# Audio_Codecs_v1.net
KiCad netlist of a schematic drawn in Altium Designer
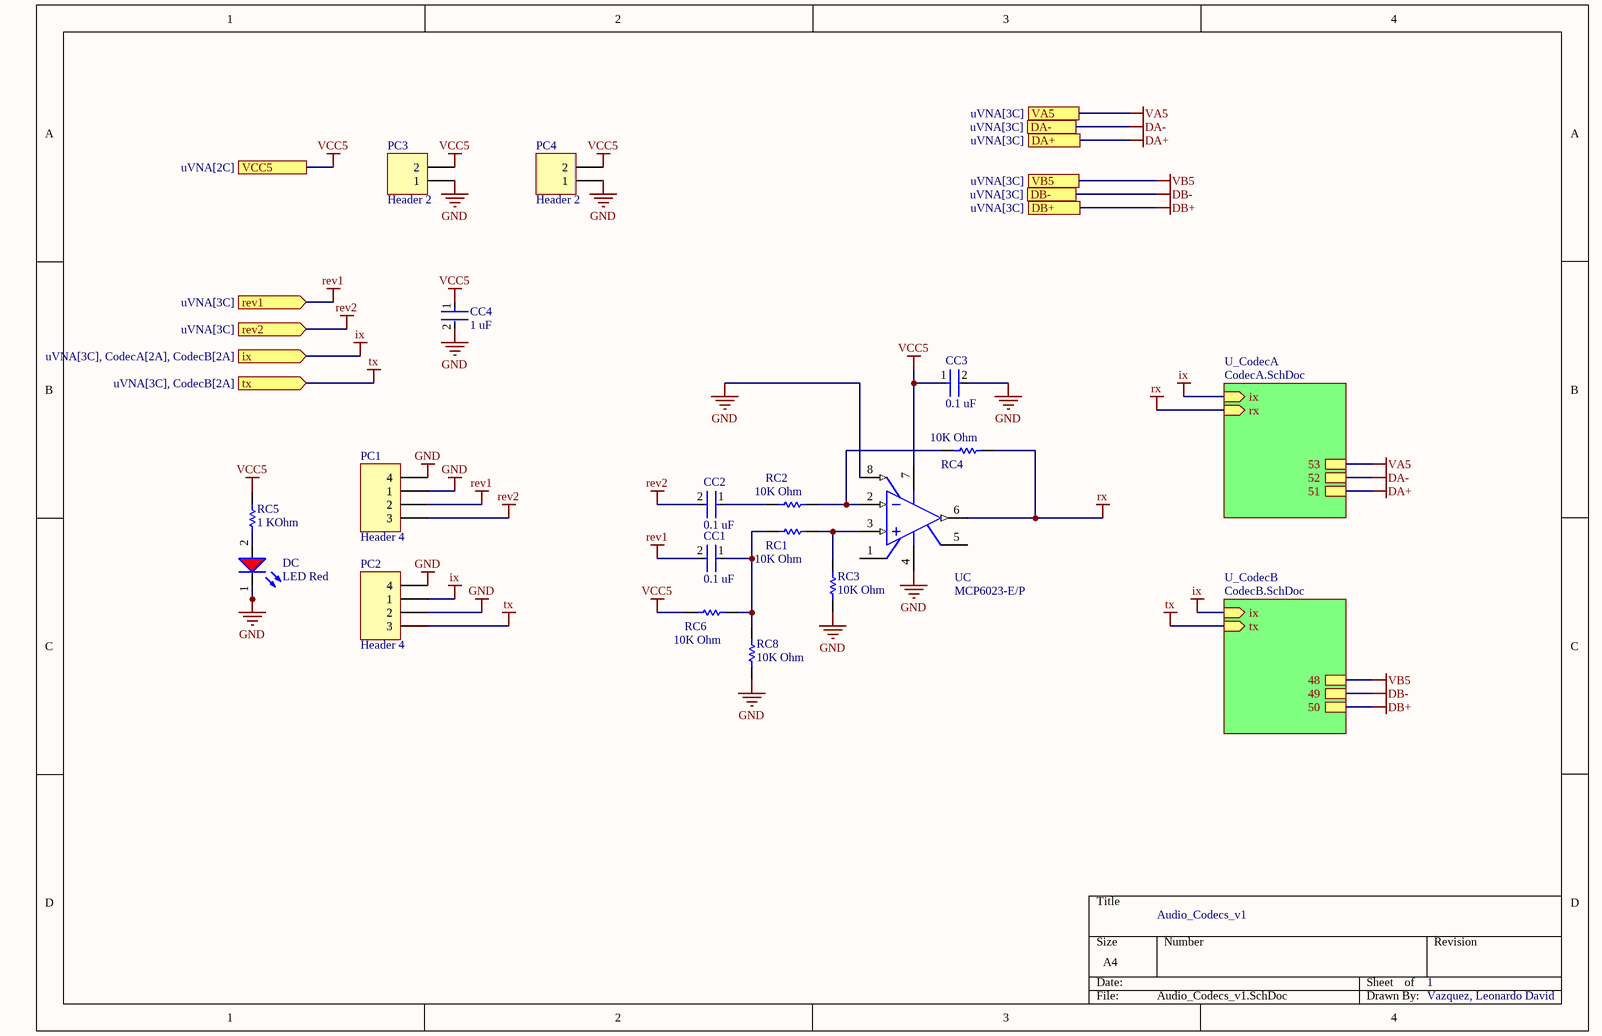
[diagram p0: Audio_Codecs_v1.SchDoc]

(export (version "E")
  (design (tool "Eeschema 10.0.6"))
  (components
    (comp (ref "CC1")
      (value "0.1 uF")
      (footprint "FP-CC0805-0_85-MFG")
      (description "CAP CER 0.1UF 50V X7R 0805")
      (fields (field (name "TOLERANCE") "0.1") (field (name "MANUFACTURER PART NUMBER") "CC0805KRX7R9BB104"))
      (libsource (lib "Altium Content Vault") (part "11868f565c42a9108669ba33697ecf6"))
    )
    (comp (ref "CC2")
      (value "0.1 uF")
      (footprint "FP-CC0805-0_85-MFG")
      (description "CAP CER 0.1UF 50V X7R 0805")
      (fields (field (name "TOLERANCE") "0.1") (field (name "MANUFACTURER PART NUMBER") "CC0805KRX7R9BB104"))
      (libsource (lib "Altium Content Vault") (part "11868f565c42a9108669ba33697ecf6"))
    )
    (comp (ref "CC3")
      (value "0.1 uF")
      (footprint "FP-CC0805-0_85-MFG")
      (description "CAP CER 0.1UF 50V X7R 0805")
      (fields (field (name "TOLERANCE") "0.1") (field (name "MANUFACTURER PART NUMBER") "CC0805KRX7R9BB104"))
      (libsource (lib "Altium Content Vault") (part "11868f565c42a9108669ba33697ecf6"))
    )
    (comp (ref "CC4")
      (value "1 uF")
      (footprint "FP-CC0805-0_85-MFG")
      (description "CAP CER 0.1UF 50V X7R 0805")
      (fields (field (name "TOLERANCE") "0.1") (field (name "MANUFACTURER PART NUMBER") "CC0805KRX7R9BB104"))
      (libsource (lib "Altium Content Vault") (part "11868f565c42a9108669ba33697ecf6"))
    )
    (comp (ref "DC")
      (value "LED Red")
      (footprint "WL-SMCW_0805_150080xx75000")
      (libsource (lib "Altium Content Vault") (part "LED_Red_2A-1K"))
    )
    (comp (ref "PC1")
      (value "Header 4")
      (footprint "HDR1X4")
      (description "Header, 4-Pin")
      (fields (field (name "PUBLISHER") "Altium Limited"))
      (libsource (lib "Miscellaneous Connectors") (part "Header 4"))
    )
    (comp (ref "PC2")
      (value "Header 4")
      (footprint "HDR1X4")
      (description "Header, 4-Pin")
      (fields (field (name "PUBLISHER") "Altium Limited"))
      (libsource (lib "Miscellaneous Connectors") (part "Header 4"))
    )
    (comp (ref "PC3")
      (value "Header 2")
      (footprint "HDR1X2")
      (description "Header, 2-Pin")
      (fields (field (name "PUBLISHER") "Altium Limited"))
      (libsource (lib "Miscellaneous Connectors") (part "Header 2"))
    )
    (comp (ref "PC4")
      (value "Header 2")
      (footprint "HDR1X2")
      (description "Header, 2-Pin")
      (fields (field (name "PUBLISHER") "Altium Limited"))
      (libsource (lib "Miscellaneous Connectors") (part "Header 2"))
    )
    (comp (ref "RC1")
      (value "10K Ohm")
      (footprint "RESC2013X60X40ML20T25")
      (fields (field (name "MANUFACTURER") "Panasonic") (field (name "PART NUMBER") "ERA6AEB101V"))
      (libsource (lib "Altium Content Vault") (part "RES"))
    )
    (comp (ref "RC2")
      (value "10K Ohm")
      (footprint "RESC2013X60X40ML20T25")
      (fields (field (name "MANUFACTURER") "Panasonic") (field (name "PART NUMBER") "ERA6AEB101V"))
      (libsource (lib "Altium Content Vault") (part "RES"))
    )
    (comp (ref "RC3")
      (value "10K Ohm")
      (footprint "RESC2013X60X40ML20T25")
      (fields (field (name "MANUFACTURER") "Panasonic") (field (name "PART NUMBER") "ERA6AEB101V"))
      (libsource (lib "Altium Content Vault") (part "RES"))
    )
    (comp (ref "RC4")
      (value "10K Ohm")
      (footprint "RESC2013X60X40ML20T25")
      (fields (field (name "MANUFACTURER") "Panasonic") (field (name "PART NUMBER") "ERA6AEB101V"))
      (libsource (lib "Altium Content Vault") (part "RES"))
    )
    (comp (ref "RC5")
      (value "1 KOhm")
      (footprint "RESC2013X60X40ML20T25")
      (fields (field (name "MANUFACTURER") "Panasonic") (field (name "PART NUMBER") "ERA6AEB101V"))
      (libsource (lib "Altium Content Vault") (part "RES"))
    )
    (comp (ref "RC6")
      (value "10K Ohm")
      (footprint "RESC2013X60X40ML20T25")
      (fields (field (name "MANUFACTURER") "Panasonic") (field (name "PART NUMBER") "ERA6AEB101V"))
      (libsource (lib "Altium Content Vault") (part "RES"))
    )
    (comp (ref "RC8")
      (value "10K Ohm")
      (footprint "RESC2013X60X40ML20T25")
      (fields (field (name "MANUFACTURER") "Panasonic") (field (name "PART NUMBER") "ERA6AEB101V"))
      (libsource (lib "Altium Content Vault") (part "RES"))
    )
    (comp (ref "UC")
      (value "MCP6023-E/P")
      (footprint "PDIP300-P8")
      (description "None")
      (libsource (lib "Altium Content Vault") (part "AMP-OPA-MCP6023-IL8"))
    )
  )
  (nets
    (net (code "5") (name "GND") (class "Default")
      (node (ref "CC3") (pin "2") (pinfunction "2_2") (pintype "passive"))
      (node (ref "CC4") (pin "2") (pinfunction "2_2") (pintype "passive"))
      (node (ref "DC") (pin "1") (pinfunction "K_1") (pintype "passive"))
      (node (ref "PC1") (pin "1") (pinfunction "1_1") (pintype "passive"))
      (node (ref "PC1") (pin "4") (pinfunction "4_4") (pintype "passive"))
      (node (ref "PC2") (pin "2") (pinfunction "2_2") (pintype "passive"))
      (node (ref "PC2") (pin "4") (pinfunction "4_4") (pintype "passive"))
      (node (ref "PC3") (pin "1") (pinfunction "1_1") (pintype "passive"))
      (node (ref "PC4") (pin "1") (pinfunction "1_1") (pintype "passive"))
      (node (ref "RC3") (pin "2") (pinfunction "2_2") (pintype "passive"))
      (node (ref "RC8") (pin "2") (pinfunction "2_2") (pintype "passive"))
      (node (ref "UC") (pin "4") (pinfunction "VSS_4") (pintype "power_in"))
      (node (ref "UC") (pin "8") (pinfunction "~{CS}_8") (pintype "input"))
    )
    (net (code "6") (name "Net-(CC1-Pad1)") (class "Default")
      (node (ref "CC1") (pin "1") (pinfunction "1_1") (pintype "passive"))
      (node (ref "RC1") (pin "2") (pinfunction "2_2") (pintype "passive"))
      (node (ref "RC6") (pin "1") (pinfunction "1_1") (pintype "passive"))
      (node (ref "RC8") (pin "1") (pinfunction "1_1") (pintype "passive"))
    )
    (net (code "7") (name "Net-(CC2-Pad1)") (class "Default")
      (node (ref "CC2") (pin "1") (pinfunction "1_1") (pintype "passive"))
      (node (ref "RC2") (pin "2") (pinfunction "2_2") (pintype "passive"))
    )
    (net (code "8") (name "Net-(DC-A)") (class "Default")
      (node (ref "DC") (pin "2") (pinfunction "A_2") (pintype "passive"))
      (node (ref "RC5") (pin "1") (pinfunction "1_1") (pintype "passive"))
    )
    (net (code "9") (name "Net-(UC-VIN+)") (class "Default")
      (node (ref "RC1") (pin "1") (pinfunction "1_1") (pintype "passive"))
      (node (ref "RC3") (pin "1") (pinfunction "1_1") (pintype "passive"))
      (node (ref "UC") (pin "3") (pinfunction "VIN+_3") (pintype "input"))
    )
    (net (code "10") (name "Net-(UC-VIN-)") (class "Default")
      (node (ref "RC2") (pin "1") (pinfunction "1_1") (pintype "passive"))
      (node (ref "RC4") (pin "2") (pinfunction "2_2") (pintype "passive"))
      (node (ref "UC") (pin "2") (pinfunction "VIN-_2") (pintype "input"))
    )
    (net (code "13") (name "VCC5") (class "Default")
      (node (ref "CC3") (pin "1") (pinfunction "1_1") (pintype "passive"))
      (node (ref "CC4") (pin "1") (pinfunction "1_1") (pintype "passive"))
      (node (ref "PC3") (pin "2") (pinfunction "2_2") (pintype "passive"))
      (node (ref "PC4") (pin "2") (pinfunction "2_2") (pintype "passive"))
      (node (ref "RC5") (pin "2") (pinfunction "2_2") (pintype "passive"))
      (node (ref "RC6") (pin "2") (pinfunction "2_2") (pintype "passive"))
      (node (ref "UC") (pin "7") (pinfunction "VDD_7") (pintype "power_in"))
    )
    (net (code "14") (name "ix") (class "Default")
      (node (ref "PC2") (pin "1") (pinfunction "1_1") (pintype "passive"))
    )
    (net (code "15") (name "rev1") (class "Default")
      (node (ref "CC1") (pin "2") (pinfunction "2_2") (pintype "passive"))
      (node (ref "PC1") (pin "2") (pinfunction "2_2") (pintype "passive"))
    )
    (net (code "16") (name "rev2") (class "Default")
      (node (ref "CC2") (pin "2") (pinfunction "2_2") (pintype "passive"))
      (node (ref "PC1") (pin "3") (pinfunction "3_3") (pintype "passive"))
    )
    (net (code "17") (name "rx") (class "Default")
      (node (ref "RC4") (pin "1") (pinfunction "1_1") (pintype "passive"))
      (node (ref "UC") (pin "6") (pinfunction "VOUT_6") (pintype "output"))
    )
    (net (code "18") (name "tx") (class "Default")
      (node (ref "PC2") (pin "3") (pinfunction "3_3") (pintype "passive"))
    )
    (net (code "19") (name "unconnected-(UC-NC-Pad1)") (class "Default")
      (node (ref "UC") (pin "1") (pinfunction "NC_1") (pintype "passive"))
    )
    (net (code "20") (name "unconnected-(UC-VREF-Pad5)") (class "Default")
      (node (ref "UC") (pin "5") (pinfunction "VREF_5") (pintype "power_in"))
    )
  )
)
